# B152A.net
KiCad netlist of a schematic drawn in EAGLE
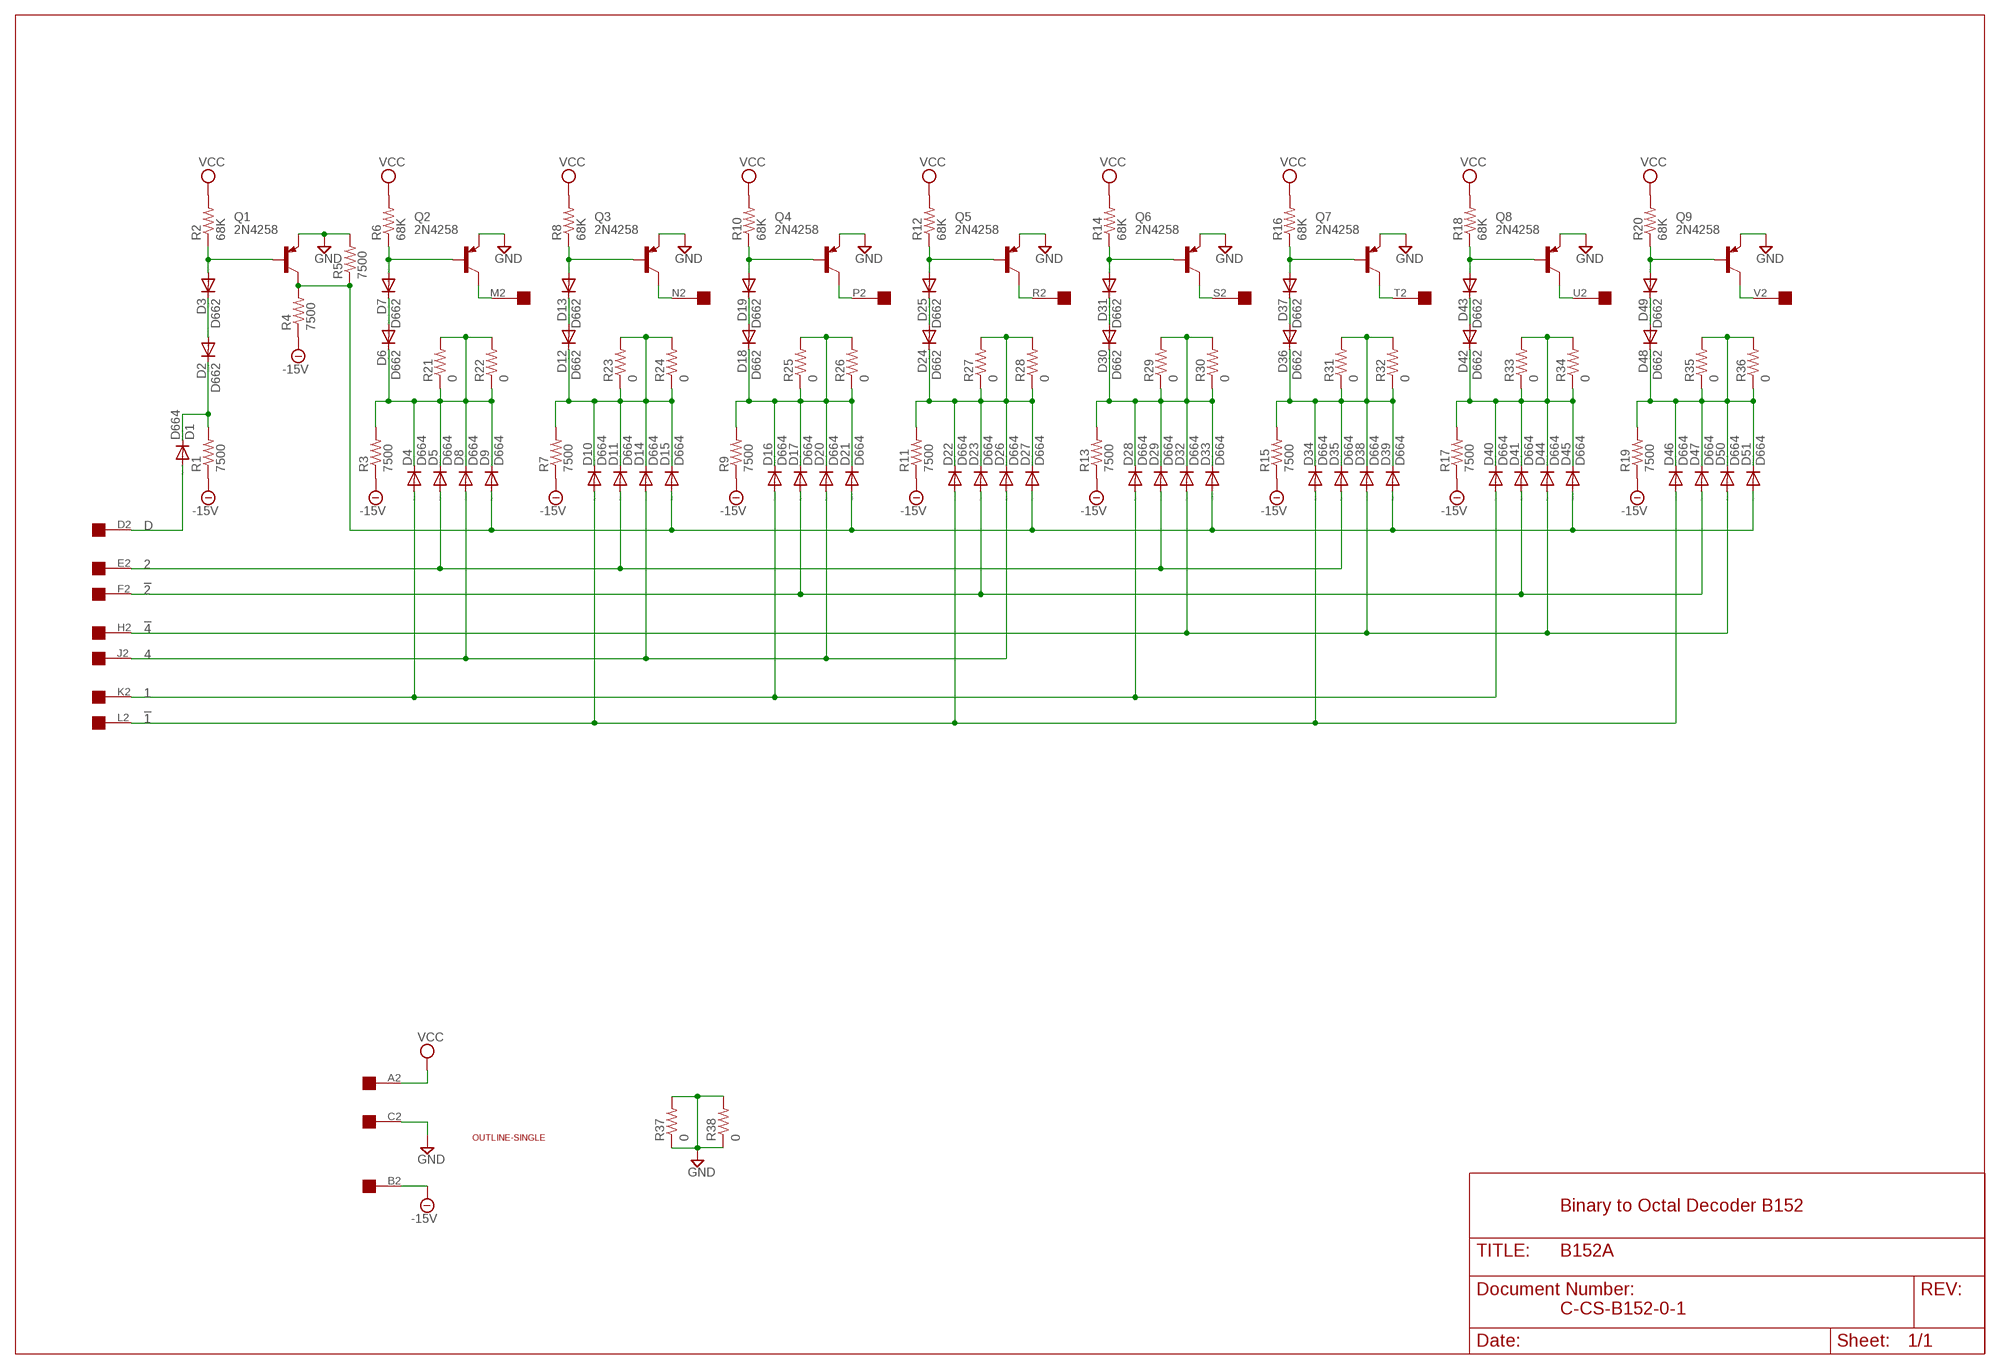
[diagram p0: schematic, sheet 1]

(export (version "E")
  (design (tool "Eeschema 10.0.6"))
  (components
    (comp (ref "D1")
      (value "D664")
      (footprint "eagle-import:DO35-10")
      (libsource (lib "eagle-import") (part "DIODE-DO35-10"))
    )
    (comp (ref "D2")
      (value "D662")
      (footprint "eagle-import:DO35-10")
      (libsource (lib "eagle-import") (part "DIODE-DO35-10"))
    )
    (comp (ref "D3")
      (value "D662")
      (footprint "eagle-import:DO35-10")
      (libsource (lib "eagle-import") (part "DIODE-DO35-10"))
    )
    (comp (ref "D4")
      (value "D664")
      (footprint "eagle-import:DO35-10")
      (libsource (lib "eagle-import") (part "DIODE-DO35-10"))
    )
    (comp (ref "D5")
      (value "D664")
      (footprint "eagle-import:DO35-10")
      (libsource (lib "eagle-import") (part "DIODE-DO35-10"))
    )
    (comp (ref "D6")
      (value "D662")
      (footprint "eagle-import:DO35-10")
      (libsource (lib "eagle-import") (part "DIODE-DO35-10"))
    )
    (comp (ref "D7")
      (value "D662")
      (footprint "eagle-import:DO35-10")
      (libsource (lib "eagle-import") (part "DIODE-DO35-10"))
    )
    (comp (ref "D8")
      (value "D664")
      (footprint "eagle-import:DO35-10")
      (libsource (lib "eagle-import") (part "DIODE-DO35-10"))
    )
    (comp (ref "D9")
      (value "D664")
      (footprint "eagle-import:DO35-10")
      (libsource (lib "eagle-import") (part "DIODE-DO35-10"))
    )
    (comp (ref "D10")
      (value "D664")
      (footprint "eagle-import:DO35-10")
      (libsource (lib "eagle-import") (part "DIODE-DO35-10"))
    )
    (comp (ref "D11")
      (value "D664")
      (footprint "eagle-import:DO35-10")
      (libsource (lib "eagle-import") (part "DIODE-DO35-10"))
    )
    (comp (ref "D12")
      (value "D662")
      (footprint "eagle-import:DO35-10")
      (libsource (lib "eagle-import") (part "DIODE-DO35-10"))
    )
    (comp (ref "D13")
      (value "D662")
      (footprint "eagle-import:DO35-10")
      (libsource (lib "eagle-import") (part "DIODE-DO35-10"))
    )
    (comp (ref "D14")
      (value "D664")
      (footprint "eagle-import:DO35-10")
      (libsource (lib "eagle-import") (part "DIODE-DO35-10"))
    )
    (comp (ref "D15")
      (value "D664")
      (footprint "eagle-import:DO35-10")
      (libsource (lib "eagle-import") (part "DIODE-DO35-10"))
    )
    (comp (ref "D16")
      (value "D664")
      (footprint "eagle-import:DO35-10")
      (libsource (lib "eagle-import") (part "DIODE-DO35-10"))
    )
    (comp (ref "D17")
      (value "D664")
      (footprint "eagle-import:DO35-10")
      (libsource (lib "eagle-import") (part "DIODE-DO35-10"))
    )
    (comp (ref "D18")
      (value "D662")
      (footprint "eagle-import:DO35-10")
      (libsource (lib "eagle-import") (part "DIODE-DO35-10"))
    )
    (comp (ref "D19")
      (value "D662")
      (footprint "eagle-import:DO35-10")
      (libsource (lib "eagle-import") (part "DIODE-DO35-10"))
    )
    (comp (ref "D20")
      (value "D664")
      (footprint "eagle-import:DO35-10")
      (libsource (lib "eagle-import") (part "DIODE-DO35-10"))
    )
    (comp (ref "D21")
      (value "D664")
      (footprint "eagle-import:DO35-10")
      (libsource (lib "eagle-import") (part "DIODE-DO35-10"))
    )
    (comp (ref "D22")
      (value "D664")
      (footprint "eagle-import:DO35-10")
      (libsource (lib "eagle-import") (part "DIODE-DO35-10"))
    )
    (comp (ref "D23")
      (value "D664")
      (footprint "eagle-import:DO35-10")
      (libsource (lib "eagle-import") (part "DIODE-DO35-10"))
    )
    (comp (ref "D24")
      (value "D662")
      (footprint "eagle-import:DO35-10")
      (libsource (lib "eagle-import") (part "DIODE-DO35-10"))
    )
    (comp (ref "D25")
      (value "D662")
      (footprint "eagle-import:DO35-10")
      (libsource (lib "eagle-import") (part "DIODE-DO35-10"))
    )
    (comp (ref "D26")
      (value "D664")
      (footprint "eagle-import:DO35-10")
      (libsource (lib "eagle-import") (part "DIODE-DO35-10"))
    )
    (comp (ref "D27")
      (value "D664")
      (footprint "eagle-import:DO35-10")
      (libsource (lib "eagle-import") (part "DIODE-DO35-10"))
    )
    (comp (ref "D28")
      (value "D664")
      (footprint "eagle-import:DO35-10")
      (libsource (lib "eagle-import") (part "DIODE-DO35-10"))
    )
    (comp (ref "D29")
      (value "D664")
      (footprint "eagle-import:DO35-10")
      (libsource (lib "eagle-import") (part "DIODE-DO35-10"))
    )
    (comp (ref "D30")
      (value "D662")
      (footprint "eagle-import:DO35-10")
      (libsource (lib "eagle-import") (part "DIODE-DO35-10"))
    )
    (comp (ref "D31")
      (value "D662")
      (footprint "eagle-import:DO35-10")
      (libsource (lib "eagle-import") (part "DIODE-DO35-10"))
    )
    (comp (ref "D32")
      (value "D664")
      (footprint "eagle-import:DO35-10")
      (libsource (lib "eagle-import") (part "DIODE-DO35-10"))
    )
    (comp (ref "D33")
      (value "D664")
      (footprint "eagle-import:DO35-10")
      (libsource (lib "eagle-import") (part "DIODE-DO35-10"))
    )
    (comp (ref "D34")
      (value "D664")
      (footprint "eagle-import:DO35-10")
      (libsource (lib "eagle-import") (part "DIODE-DO35-10"))
    )
    (comp (ref "D35")
      (value "D664")
      (footprint "eagle-import:DO35-10")
      (libsource (lib "eagle-import") (part "DIODE-DO35-10"))
    )
    (comp (ref "D36")
      (value "D662")
      (footprint "eagle-import:DO35-10")
      (libsource (lib "eagle-import") (part "DIODE-DO35-10"))
    )
    (comp (ref "D37")
      (value "D662")
      (footprint "eagle-import:DO35-10")
      (libsource (lib "eagle-import") (part "DIODE-DO35-10"))
    )
    (comp (ref "D38")
      (value "D664")
      (footprint "eagle-import:DO35-10")
      (libsource (lib "eagle-import") (part "DIODE-DO35-10"))
    )
    (comp (ref "D39")
      (value "D664")
      (footprint "eagle-import:DO35-10")
      (libsource (lib "eagle-import") (part "DIODE-DO35-10"))
    )
    (comp (ref "D40")
      (value "D664")
      (footprint "eagle-import:DO35-10")
      (libsource (lib "eagle-import") (part "DIODE-DO35-10"))
    )
    (comp (ref "D41")
      (value "D664")
      (footprint "eagle-import:DO35-10")
      (libsource (lib "eagle-import") (part "DIODE-DO35-10"))
    )
    (comp (ref "D42")
      (value "D662")
      (footprint "eagle-import:DO35-10")
      (libsource (lib "eagle-import") (part "DIODE-DO35-10"))
    )
    (comp (ref "D43")
      (value "D662")
      (footprint "eagle-import:DO35-10")
      (libsource (lib "eagle-import") (part "DIODE-DO35-10"))
    )
    (comp (ref "D44")
      (value "D664")
      (footprint "eagle-import:DO35-10")
      (libsource (lib "eagle-import") (part "DIODE-DO35-10"))
    )
    (comp (ref "D45")
      (value "D664")
      (footprint "eagle-import:DO35-10")
      (libsource (lib "eagle-import") (part "DIODE-DO35-10"))
    )
    (comp (ref "D46")
      (value "D664")
      (footprint "eagle-import:DO35-10")
      (libsource (lib "eagle-import") (part "DIODE-DO35-10"))
    )
    (comp (ref "D47")
      (value "D664")
      (footprint "eagle-import:DO35-10")
      (libsource (lib "eagle-import") (part "DIODE-DO35-10"))
    )
    (comp (ref "D48")
      (value "D662")
      (footprint "eagle-import:DO35-10")
      (libsource (lib "eagle-import") (part "DIODE-DO35-10"))
    )
    (comp (ref "D49")
      (value "D662")
      (footprint "eagle-import:DO35-10")
      (libsource (lib "eagle-import") (part "DIODE-DO35-10"))
    )
    (comp (ref "D50")
      (value "D664")
      (footprint "eagle-import:DO35-10")
      (libsource (lib "eagle-import") (part "DIODE-DO35-10"))
    )
    (comp (ref "D51")
      (value "D664")
      (footprint "eagle-import:DO35-10")
      (libsource (lib "eagle-import") (part "DIODE-DO35-10"))
    )
    (comp (ref "Q1")
      (value "2N4258")
      (footprint "eagle-import:TO5")
      (libsource (lib "eagle-import") (part "-PNP-TO5"))
    )
    (comp (ref "Q2")
      (value "2N4258")
      (footprint "eagle-import:TO5")
      (libsource (lib "eagle-import") (part "-PNP-TO5"))
    )
    (comp (ref "Q3")
      (value "2N4258")
      (footprint "eagle-import:TO5")
      (libsource (lib "eagle-import") (part "-PNP-TO5"))
    )
    (comp (ref "Q4")
      (value "2N4258")
      (footprint "eagle-import:TO5")
      (libsource (lib "eagle-import") (part "-PNP-TO5"))
    )
    (comp (ref "Q5")
      (value "2N4258")
      (footprint "eagle-import:TO5")
      (libsource (lib "eagle-import") (part "-PNP-TO5"))
    )
    (comp (ref "Q6")
      (value "2N4258")
      (footprint "eagle-import:TO5")
      (libsource (lib "eagle-import") (part "-PNP-TO5"))
    )
    (comp (ref "Q7")
      (value "2N4258")
      (footprint "eagle-import:TO5")
      (libsource (lib "eagle-import") (part "-PNP-TO5"))
    )
    (comp (ref "Q8")
      (value "2N4258")
      (footprint "eagle-import:TO5")
      (libsource (lib "eagle-import") (part "-PNP-TO5"))
    )
    (comp (ref "Q9")
      (value "2N4258")
      (footprint "eagle-import:TO5")
      (libsource (lib "eagle-import") (part "-PNP-TO5"))
    )
    (comp (ref "R1")
      (value "7500")
      (footprint "eagle-import:0207_10")
      (libsource (lib "eagle-import") (part "R-US_0207/10"))
    )
    (comp (ref "R2")
      (value "68K")
      (footprint "eagle-import:0207_10")
      (libsource (lib "eagle-import") (part "R-US_0207/10"))
    )
    (comp (ref "R3")
      (value "7500")
      (footprint "eagle-import:0207_10")
      (libsource (lib "eagle-import") (part "R-US_0207/10"))
    )
    (comp (ref "R4")
      (value "7500")
      (footprint "eagle-import:0207_10")
      (libsource (lib "eagle-import") (part "R-US_0207/10"))
    )
    (comp (ref "R5")
      (value "7500")
      (footprint "eagle-import:0207_10")
      (libsource (lib "eagle-import") (part "R-US_0207/10"))
    )
    (comp (ref "R6")
      (value "68K")
      (footprint "eagle-import:0207_10")
      (libsource (lib "eagle-import") (part "R-US_0207/10"))
    )
    (comp (ref "R7")
      (value "7500")
      (footprint "eagle-import:0207_10")
      (libsource (lib "eagle-import") (part "R-US_0207/10"))
    )
    (comp (ref "R8")
      (value "68K")
      (footprint "eagle-import:0207_10")
      (libsource (lib "eagle-import") (part "R-US_0207/10"))
    )
    (comp (ref "R9")
      (value "7500")
      (footprint "eagle-import:0207_10")
      (libsource (lib "eagle-import") (part "R-US_0207/10"))
    )
    (comp (ref "R10")
      (value "68K")
      (footprint "eagle-import:0207_10")
      (libsource (lib "eagle-import") (part "R-US_0207/10"))
    )
    (comp (ref "R11")
      (value "7500")
      (footprint "eagle-import:0207_10")
      (libsource (lib "eagle-import") (part "R-US_0207/10"))
    )
    (comp (ref "R12")
      (value "68K")
      (footprint "eagle-import:0207_10")
      (libsource (lib "eagle-import") (part "R-US_0207/10"))
    )
    (comp (ref "R13")
      (value "7500")
      (footprint "eagle-import:0207_10")
      (libsource (lib "eagle-import") (part "R-US_0207/10"))
    )
    (comp (ref "R14")
      (value "68K")
      (footprint "eagle-import:0207_10")
      (libsource (lib "eagle-import") (part "R-US_0207/10"))
    )
    (comp (ref "R15")
      (value "7500")
      (footprint "eagle-import:0207_10")
      (libsource (lib "eagle-import") (part "R-US_0207/10"))
    )
    (comp (ref "R16")
      (value "68K")
      (footprint "eagle-import:0207_10")
      (libsource (lib "eagle-import") (part "R-US_0207/10"))
    )
    (comp (ref "R17")
      (value "7500")
      (footprint "eagle-import:0207_10")
      (libsource (lib "eagle-import") (part "R-US_0207/10"))
    )
    (comp (ref "R18")
      (value "68K")
      (footprint "eagle-import:0207_10")
      (libsource (lib "eagle-import") (part "R-US_0207/10"))
    )
    (comp (ref "R19")
      (value "7500")
      (footprint "eagle-import:0207_10")
      (libsource (lib "eagle-import") (part "R-US_0207/10"))
    )
    (comp (ref "R20")
      (value "68K")
      (footprint "eagle-import:0207_10")
      (libsource (lib "eagle-import") (part "R-US_0207/10"))
    )
    (comp (ref "R21")
      (value "0")
      (footprint "eagle-import:0207_10")
      (libsource (lib "eagle-import") (part "R-US_0207/10"))
    )
    (comp (ref "R22")
      (value "0")
      (footprint "eagle-import:0207_10")
      (libsource (lib "eagle-import") (part "R-US_0207/10"))
    )
    (comp (ref "R23")
      (value "0")
      (footprint "eagle-import:0207_10")
      (libsource (lib "eagle-import") (part "R-US_0207/10"))
    )
    (comp (ref "R24")
      (value "0")
      (footprint "eagle-import:0207_10")
      (libsource (lib "eagle-import") (part "R-US_0207/10"))
    )
    (comp (ref "R25")
      (value "0")
      (footprint "eagle-import:0207_10")
      (libsource (lib "eagle-import") (part "R-US_0207/10"))
    )
    (comp (ref "R26")
      (value "0")
      (footprint "eagle-import:0207_10")
      (libsource (lib "eagle-import") (part "R-US_0207/10"))
    )
    (comp (ref "R27")
      (value "0")
      (footprint "eagle-import:0207_10")
      (libsource (lib "eagle-import") (part "R-US_0207/10"))
    )
    (comp (ref "R28")
      (value "0")
      (footprint "eagle-import:0207_10")
      (libsource (lib "eagle-import") (part "R-US_0207/10"))
    )
    (comp (ref "R29")
      (value "0")
      (footprint "eagle-import:0207_10")
      (libsource (lib "eagle-import") (part "R-US_0207/10"))
    )
    (comp (ref "R30")
      (value "0")
      (footprint "eagle-import:0207_10")
      (libsource (lib "eagle-import") (part "R-US_0207/10"))
    )
    (comp (ref "R31")
      (value "0")
      (footprint "eagle-import:0207_10")
      (libsource (lib "eagle-import") (part "R-US_0207/10"))
    )
    (comp (ref "R32")
      (value "0")
      (footprint "eagle-import:0207_10")
      (libsource (lib "eagle-import") (part "R-US_0207/10"))
    )
    (comp (ref "R33")
      (value "0")
      (footprint "eagle-import:0207_10")
      (libsource (lib "eagle-import") (part "R-US_0207/10"))
    )
    (comp (ref "R34")
      (value "0")
      (footprint "eagle-import:0207_10")
      (libsource (lib "eagle-import") (part "R-US_0207/10"))
    )
    (comp (ref "R35")
      (value "0")
      (footprint "eagle-import:0207_10")
      (libsource (lib "eagle-import") (part "R-US_0207/10"))
    )
    (comp (ref "R36")
      (value "0")
      (footprint "eagle-import:0207_10")
      (libsource (lib "eagle-import") (part "R-US_0207/10"))
    )
    (comp (ref "R37")
      (value "0")
      (footprint "eagle-import:0207_10")
      (libsource (lib "eagle-import") (part "R-US_0207/10"))
    )
    (comp (ref "R38")
      (value "0")
      (footprint "eagle-import:0207_10")
      (libsource (lib "eagle-import") (part "R-US_0207/10"))
    )
    (comp (ref "U$1")
      (value "OUTLINE-SINGLE")
      (footprint "eagle-import:SINGLE")
      (libsource (lib "eagle-import") (part "OUTLINE-SINGLE"))
    )
    (comp (ref "U$2")
      (value "EDGE-1")
      (footprint "eagle-import:EDGE-CON1")
      (libsource (lib "eagle-import") (part "EDGE-1"))
    )
  )
  (nets
    (net (code "1") (name "-15V") (class "Default")
      (node (ref "R1") (pin "1") (pinfunction "1_1") (pintype "passive"))
      (node (ref "R11") (pin "1") (pinfunction "1_1") (pintype "passive"))
      (node (ref "R13") (pin "1") (pinfunction "1_1") (pintype "passive"))
      (node (ref "R15") (pin "1") (pinfunction "1_1") (pintype "passive"))
      (node (ref "R17") (pin "1") (pinfunction "1_1") (pintype "passive"))
      (node (ref "R19") (pin "1") (pinfunction "1_1") (pintype "passive"))
      (node (ref "R3") (pin "1") (pinfunction "1_1") (pintype "passive"))
      (node (ref "R4") (pin "1") (pinfunction "1_1") (pintype "passive"))
      (node (ref "R7") (pin "1") (pinfunction "1_1") (pintype "passive"))
      (node (ref "R9") (pin "1") (pinfunction "1_1") (pintype "passive"))
      (node (ref "U$2") (pin "B2") (pinfunction "1_B2") (pintype "bidirectional"))
    )
    (net (code "2") (name "/1") (class "Default")
      (node (ref "D16") (pin "A") (pinfunction "A_A") (pintype "passive"))
      (node (ref "D28") (pin "A") (pinfunction "A_A") (pintype "passive"))
      (node (ref "D4") (pin "A") (pinfunction "A_A") (pintype "passive"))
      (node (ref "D40") (pin "A") (pinfunction "A_A") (pintype "passive"))
      (node (ref "U$2") (pin "K2") (pinfunction "1_K2") (pintype "bidirectional"))
    )
    (net (code "3") (name "/2") (class "Default")
      (node (ref "D11") (pin "A") (pinfunction "A_A") (pintype "passive"))
      (node (ref "D29") (pin "A") (pinfunction "A_A") (pintype "passive"))
      (node (ref "D35") (pin "A") (pinfunction "A_A") (pintype "passive"))
      (node (ref "D5") (pin "A") (pinfunction "A_A") (pintype "passive"))
      (node (ref "U$2") (pin "E2") (pinfunction "1_E2") (pintype "bidirectional"))
    )
    (net (code "4") (name "/4") (class "Default")
      (node (ref "D14") (pin "A") (pinfunction "A_A") (pintype "passive"))
      (node (ref "D20") (pin "A") (pinfunction "A_A") (pintype "passive"))
      (node (ref "D26") (pin "A") (pinfunction "A_A") (pintype "passive"))
      (node (ref "D8") (pin "A") (pinfunction "A_A") (pintype "passive"))
      (node (ref "U$2") (pin "J2") (pinfunction "1_J2") (pintype "bidirectional"))
    )
    (net (code "5") (name "/D") (class "Default")
      (node (ref "D1") (pin "A") (pinfunction "A_A") (pintype "passive"))
      (node (ref "U$2") (pin "D2") (pinfunction "1_D2") (pintype "bidirectional"))
    )
    (net (code "6") (name "/~{1}") (class "Default")
      (node (ref "D10") (pin "A") (pinfunction "A_A") (pintype "passive"))
      (node (ref "D22") (pin "A") (pinfunction "A_A") (pintype "passive"))
      (node (ref "D34") (pin "A") (pinfunction "A_A") (pintype "passive"))
      (node (ref "D46") (pin "A") (pinfunction "A_A") (pintype "passive"))
      (node (ref "U$2") (pin "L2") (pinfunction "1_L2") (pintype "bidirectional"))
    )
    (net (code "7") (name "/~{2}") (class "Default")
      (node (ref "D17") (pin "A") (pinfunction "A_A") (pintype "passive"))
      (node (ref "D23") (pin "A") (pinfunction "A_A") (pintype "passive"))
      (node (ref "D41") (pin "A") (pinfunction "A_A") (pintype "passive"))
      (node (ref "D47") (pin "A") (pinfunction "A_A") (pintype "passive"))
      (node (ref "U$2") (pin "F2") (pinfunction "1_F2") (pintype "bidirectional"))
    )
    (net (code "8") (name "/~{4}") (class "Default")
      (node (ref "D32") (pin "A") (pinfunction "A_A") (pintype "passive"))
      (node (ref "D38") (pin "A") (pinfunction "A_A") (pintype "passive"))
      (node (ref "D44") (pin "A") (pinfunction "A_A") (pintype "passive"))
      (node (ref "D50") (pin "A") (pinfunction "A_A") (pintype "passive"))
      (node (ref "U$2") (pin "H2") (pinfunction "1_H2") (pintype "bidirectional"))
    )
    (net (code "9") (name "GND") (class "Default")
      (node (ref "Q1") (pin "1") (pinfunction "E_1") (pintype "passive"))
      (node (ref "Q2") (pin "1") (pinfunction "E_1") (pintype "passive"))
      (node (ref "Q3") (pin "1") (pinfunction "E_1") (pintype "passive"))
      (node (ref "Q4") (pin "1") (pinfunction "E_1") (pintype "passive"))
      (node (ref "Q5") (pin "1") (pinfunction "E_1") (pintype "passive"))
      (node (ref "Q6") (pin "1") (pinfunction "E_1") (pintype "passive"))
      (node (ref "Q7") (pin "1") (pinfunction "E_1") (pintype "passive"))
      (node (ref "Q8") (pin "1") (pinfunction "E_1") (pintype "passive"))
      (node (ref "Q9") (pin "1") (pinfunction "E_1") (pintype "passive"))
      (node (ref "R37") (pin "1") (pinfunction "1_1") (pintype "passive"))
      (node (ref "R37") (pin "2") (pinfunction "2_2") (pintype "passive"))
      (node (ref "R38") (pin "1") (pinfunction "1_1") (pintype "passive"))
      (node (ref "R38") (pin "2") (pinfunction "2_2") (pintype "passive"))
      (node (ref "R5") (pin "2") (pinfunction "2_2") (pintype "passive"))
      (node (ref "U$2") (pin "C2") (pinfunction "1_C2") (pintype "bidirectional"))
    )
    (net (code "10") (name "Net-(D1-PadC)") (class "Default")
      (node (ref "D1") (pin "C") (pinfunction "C_C") (pintype "passive"))
      (node (ref "D2") (pin "C") (pinfunction "C_C") (pintype "passive"))
      (node (ref "R1") (pin "2") (pinfunction "2_2") (pintype "passive"))
    )
    (net (code "11") (name "Net-(D2-PadA)") (class "Default")
      (node (ref "D2") (pin "A") (pinfunction "A_A") (pintype "passive"))
      (node (ref "D3") (pin "C") (pinfunction "C_C") (pintype "passive"))
    )
    (net (code "12") (name "Net-(D4-PadC)") (class "Default")
      (node (ref "D4") (pin "C") (pinfunction "C_C") (pintype "passive"))
      (node (ref "D5") (pin "C") (pinfunction "C_C") (pintype "passive"))
      (node (ref "D6") (pin "C") (pinfunction "C_C") (pintype "passive"))
      (node (ref "D8") (pin "C") (pinfunction "C_C") (pintype "passive"))
      (node (ref "D9") (pin "C") (pinfunction "C_C") (pintype "passive"))
      (node (ref "R21") (pin "1") (pinfunction "1_1") (pintype "passive"))
      (node (ref "R21") (pin "2") (pinfunction "2_2") (pintype "passive"))
      (node (ref "R22") (pin "1") (pinfunction "1_1") (pintype "passive"))
      (node (ref "R22") (pin "2") (pinfunction "2_2") (pintype "passive"))
      (node (ref "R3") (pin "2") (pinfunction "2_2") (pintype "passive"))
    )
    (net (code "13") (name "Net-(D6-PadA)") (class "Default")
      (node (ref "D6") (pin "A") (pinfunction "A_A") (pintype "passive"))
      (node (ref "D7") (pin "C") (pinfunction "C_C") (pintype "passive"))
    )
    (net (code "14") (name "Net-(D10-PadC)") (class "Default")
      (node (ref "D10") (pin "C") (pinfunction "C_C") (pintype "passive"))
      (node (ref "D11") (pin "C") (pinfunction "C_C") (pintype "passive"))
      (node (ref "D12") (pin "C") (pinfunction "C_C") (pintype "passive"))
      (node (ref "D14") (pin "C") (pinfunction "C_C") (pintype "passive"))
      (node (ref "D15") (pin "C") (pinfunction "C_C") (pintype "passive"))
      (node (ref "R23") (pin "1") (pinfunction "1_1") (pintype "passive"))
      (node (ref "R23") (pin "2") (pinfunction "2_2") (pintype "passive"))
      (node (ref "R24") (pin "1") (pinfunction "1_1") (pintype "passive"))
      (node (ref "R24") (pin "2") (pinfunction "2_2") (pintype "passive"))
      (node (ref "R7") (pin "2") (pinfunction "2_2") (pintype "passive"))
    )
    (net (code "15") (name "Net-(D12-PadA)") (class "Default")
      (node (ref "D12") (pin "A") (pinfunction "A_A") (pintype "passive"))
      (node (ref "D13") (pin "C") (pinfunction "C_C") (pintype "passive"))
    )
    (net (code "16") (name "Net-(D16-PadC)") (class "Default")
      (node (ref "D16") (pin "C") (pinfunction "C_C") (pintype "passive"))
      (node (ref "D17") (pin "C") (pinfunction "C_C") (pintype "passive"))
      (node (ref "D18") (pin "C") (pinfunction "C_C") (pintype "passive"))
      (node (ref "D20") (pin "C") (pinfunction "C_C") (pintype "passive"))
      (node (ref "D21") (pin "C") (pinfunction "C_C") (pintype "passive"))
      (node (ref "R25") (pin "1") (pinfunction "1_1") (pintype "passive"))
      (node (ref "R25") (pin "2") (pinfunction "2_2") (pintype "passive"))
      (node (ref "R26") (pin "1") (pinfunction "1_1") (pintype "passive"))
      (node (ref "R26") (pin "2") (pinfunction "2_2") (pintype "passive"))
      (node (ref "R9") (pin "2") (pinfunction "2_2") (pintype "passive"))
    )
    (net (code "17") (name "Net-(D18-PadA)") (class "Default")
      (node (ref "D18") (pin "A") (pinfunction "A_A") (pintype "passive"))
      (node (ref "D19") (pin "C") (pinfunction "C_C") (pintype "passive"))
    )
    (net (code "18") (name "Net-(D22-PadC)") (class "Default")
      (node (ref "D22") (pin "C") (pinfunction "C_C") (pintype "passive"))
      (node (ref "D23") (pin "C") (pinfunction "C_C") (pintype "passive"))
      (node (ref "D24") (pin "C") (pinfunction "C_C") (pintype "passive"))
      (node (ref "D26") (pin "C") (pinfunction "C_C") (pintype "passive"))
      (node (ref "D27") (pin "C") (pinfunction "C_C") (pintype "passive"))
      (node (ref "R11") (pin "2") (pinfunction "2_2") (pintype "passive"))
      (node (ref "R27") (pin "1") (pinfunction "1_1") (pintype "passive"))
      (node (ref "R27") (pin "2") (pinfunction "2_2") (pintype "passive"))
      (node (ref "R28") (pin "1") (pinfunction "1_1") (pintype "passive"))
      (node (ref "R28") (pin "2") (pinfunction "2_2") (pintype "passive"))
    )
    (net (code "19") (name "Net-(D24-PadA)") (class "Default")
      (node (ref "D24") (pin "A") (pinfunction "A_A") (pintype "passive"))
      (node (ref "D25") (pin "C") (pinfunction "C_C") (pintype "passive"))
    )
    (net (code "20") (name "Net-(D28-PadC)") (class "Default")
      (node (ref "D28") (pin "C") (pinfunction "C_C") (pintype "passive"))
      (node (ref "D29") (pin "C") (pinfunction "C_C") (pintype "passive"))
      (node (ref "D30") (pin "C") (pinfunction "C_C") (pintype "passive"))
      (node (ref "D32") (pin "C") (pinfunction "C_C") (pintype "passive"))
      (node (ref "D33") (pin "C") (pinfunction "C_C") (pintype "passive"))
      (node (ref "R13") (pin "2") (pinfunction "2_2") (pintype "passive"))
      (node (ref "R29") (pin "1") (pinfunction "1_1") (pintype "passive"))
      (node (ref "R29") (pin "2") (pinfunction "2_2") (pintype "passive"))
      (node (ref "R30") (pin "1") (pinfunction "1_1") (pintype "passive"))
      (node (ref "R30") (pin "2") (pinfunction "2_2") (pintype "passive"))
    )
    (net (code "21") (name "Net-(D30-PadA)") (class "Default")
      (node (ref "D30") (pin "A") (pinfunction "A_A") (pintype "passive"))
      (node (ref "D31") (pin "C") (pinfunction "C_C") (pintype "passive"))
    )
    (net (code "22") (name "Net-(D34-PadC)") (class "Default")
      (node (ref "D34") (pin "C") (pinfunction "C_C") (pintype "passive"))
      (node (ref "D35") (pin "C") (pinfunction "C_C") (pintype "passive"))
      (node (ref "D36") (pin "C") (pinfunction "C_C") (pintype "passive"))
      (node (ref "D38") (pin "C") (pinfunction "C_C") (pintype "passive"))
      (node (ref "D39") (pin "C") (pinfunction "C_C") (pintype "passive"))
      (node (ref "R15") (pin "2") (pinfunction "2_2") (pintype "passive"))
      (node (ref "R31") (pin "1") (pinfunction "1_1") (pintype "passive"))
      (node (ref "R31") (pin "2") (pinfunction "2_2") (pintype "passive"))
      (node (ref "R32") (pin "1") (pinfunction "1_1") (pintype "passive"))
      (node (ref "R32") (pin "2") (pinfunction "2_2") (pintype "passive"))
    )
    (net (code "23") (name "Net-(D36-PadA)") (class "Default")
      (node (ref "D36") (pin "A") (pinfunction "A_A") (pintype "passive"))
      (node (ref "D37") (pin "C") (pinfunction "C_C") (pintype "passive"))
    )
    (net (code "24") (name "Net-(D40-PadC)") (class "Default")
      (node (ref "D40") (pin "C") (pinfunction "C_C") (pintype "passive"))
      (node (ref "D41") (pin "C") (pinfunction "C_C") (pintype "passive"))
      (node (ref "D42") (pin "C") (pinfunction "C_C") (pintype "passive"))
      (node (ref "D44") (pin "C") (pinfunction "C_C") (pintype "passive"))
      (node (ref "D45") (pin "C") (pinfunction "C_C") (pintype "passive"))
      (node (ref "R17") (pin "2") (pinfunction "2_2") (pintype "passive"))
      (node (ref "R33") (pin "1") (pinfunction "1_1") (pintype "passive"))
      (node (ref "R33") (pin "2") (pinfunction "2_2") (pintype "passive"))
      (node (ref "R34") (pin "1") (pinfunction "1_1") (pintype "passive"))
      (node (ref "R34") (pin "2") (pinfunction "2_2") (pintype "passive"))
    )
    (net (code "25") (name "Net-(D42-PadA)") (class "Default")
      (node (ref "D42") (pin "A") (pinfunction "A_A") (pintype "passive"))
      (node (ref "D43") (pin "C") (pinfunction "C_C") (pintype "passive"))
    )
    (net (code "26") (name "Net-(D46-PadC)") (class "Default")
      (node (ref "D46") (pin "C") (pinfunction "C_C") (pintype "passive"))
      (node (ref "D47") (pin "C") (pinfunction "C_C") (pintype "passive"))
      (node (ref "D48") (pin "C") (pinfunction "C_C") (pintype "passive"))
      (node (ref "D50") (pin "C") (pinfunction "C_C") (pintype "passive"))
      (node (ref "D51") (pin "C") (pinfunction "C_C") (pintype "passive"))
      (node (ref "R19") (pin "2") (pinfunction "2_2") (pintype "passive"))
      (node (ref "R35") (pin "1") (pinfunction "1_1") (pintype "passive"))
      (node (ref "R35") (pin "2") (pinfunction "2_2") (pintype "passive"))
      (node (ref "R36") (pin "1") (pinfunction "1_1") (pintype "passive"))
      (node (ref "R36") (pin "2") (pinfunction "2_2") (pintype "passive"))
    )
    (net (code "27") (name "Net-(D48-PadA)") (class "Default")
      (node (ref "D48") (pin "A") (pinfunction "A_A") (pintype "passive"))
      (node (ref "D49") (pin "C") (pinfunction "C_C") (pintype "passive"))
    )
    (net (code "28") (name "Net-(Q1-B)") (class "Default")
      (node (ref "D3") (pin "A") (pinfunction "A_A") (pintype "passive"))
      (node (ref "Q1") (pin "2") (pinfunction "B_2") (pintype "passive"))
      (node (ref "R2") (pin "1") (pinfunction "1_1") (pintype "passive"))
    )
    (net (code "29") (name "Net-(Q1-C)") (class "Default")
      (node (ref "D15") (pin "A") (pinfunction "A_A") (pintype "passive"))
      (node (ref "D21") (pin "A") (pinfunction "A_A") (pintype "passive"))
      (node (ref "D27") (pin "A") (pinfunction "A_A") (pintype "passive"))
      (node (ref "D33") (pin "A") (pinfunction "A_A") (pintype "passive"))
      (node (ref "D39") (pin "A") (pinfunction "A_A") (pintype "passive"))
      (node (ref "D45") (pin "A") (pinfunction "A_A") (pintype "passive"))
      (node (ref "D51") (pin "A") (pinfunction "A_A") (pintype "passive"))
      (node (ref "D9") (pin "A") (pinfunction "A_A") (pintype "passive"))
      (node (ref "Q1") (pin "3") (pinfunction "C_3") (pintype "passive"))
      (node (ref "R4") (pin "2") (pinfunction "2_2") (pintype "passive"))
      (node (ref "R5") (pin "1") (pinfunction "1_1") (pintype "passive"))
    )
    (net (code "30") (name "Net-(Q2-B)") (class "Default")
      (node (ref "D7") (pin "A") (pinfunction "A_A") (pintype "passive"))
      (node (ref "Q2") (pin "2") (pinfunction "B_2") (pintype "passive"))
      (node (ref "R6") (pin "1") (pinfunction "1_1") (pintype "passive"))
    )
    (net (code "31") (name "Net-(Q2-C)") (class "Default")
      (node (ref "Q2") (pin "3") (pinfunction "C_3") (pintype "passive"))
      (node (ref "U$2") (pin "M2") (pinfunction "1_M2") (pintype "bidirectional"))
    )
    (net (code "32") (name "Net-(Q3-B)") (class "Default")
      (node (ref "D13") (pin "A") (pinfunction "A_A") (pintype "passive"))
      (node (ref "Q3") (pin "2") (pinfunction "B_2") (pintype "passive"))
      (node (ref "R8") (pin "1") (pinfunction "1_1") (pintype "passive"))
    )
    (net (code "33") (name "Net-(Q3-C)") (class "Default")
      (node (ref "Q3") (pin "3") (pinfunction "C_3") (pintype "passive"))
      (node (ref "U$2") (pin "N2") (pinfunction "1_N2") (pintype "bidirectional"))
    )
    (net (code "34") (name "Net-(Q4-B)") (class "Default")
      (node (ref "D19") (pin "A") (pinfunction "A_A") (pintype "passive"))
      (node (ref "Q4") (pin "2") (pinfunction "B_2") (pintype "passive"))
      (node (ref "R10") (pin "1") (pinfunction "1_1") (pintype "passive"))
    )
    (net (code "35") (name "Net-(Q4-C)") (class "Default")
      (node (ref "Q4") (pin "3") (pinfunction "C_3") (pintype "passive"))
      (node (ref "U$2") (pin "P2") (pinfunction "1_P2") (pintype "bidirectional"))
    )
    (net (code "36") (name "Net-(Q5-B)") (class "Default")
      (node (ref "D25") (pin "A") (pinfunction "A_A") (pintype "passive"))
      (node (ref "Q5") (pin "2") (pinfunction "B_2") (pintype "passive"))
      (node (ref "R12") (pin "1") (pinfunction "1_1") (pintype "passive"))
    )
    (net (code "37") (name "Net-(Q5-C)") (class "Default")
      (node (ref "Q5") (pin "3") (pinfunction "C_3") (pintype "passive"))
      (node (ref "U$2") (pin "R2") (pinfunction "1_R2") (pintype "bidirectional"))
    )
    (net (code "38") (name "Net-(Q6-B)") (class "Default")
      (node (ref "D31") (pin "A") (pinfunction "A_A") (pintype "passive"))
      (node (ref "Q6") (pin "2") (pinfunction "B_2") (pintype "passive"))
      (node (ref "R14") (pin "1") (pinfunction "1_1") (pintype "passive"))
    )
    (net (code "39") (name "Net-(Q6-C)") (class "Default")
      (node (ref "Q6") (pin "3") (pinfunction "C_3") (pintype "passive"))
      (node (ref "U$2") (pin "S2") (pinfunction "1_S2") (pintype "bidirectional"))
    )
    (net (code "40") (name "Net-(Q7-B)") (class "Default")
      (node (ref "D37") (pin "A") (pinfunction "A_A") (pintype "passive"))
      (node (ref "Q7") (pin "2") (pinfunction "B_2") (pintype "passive"))
      (node (ref "R16") (pin "1") (pinfunction "1_1") (pintype "passive"))
    )
    (net (code "41") (name "Net-(Q7-C)") (class "Default")
      (node (ref "Q7") (pin "3") (pinfunction "C_3") (pintype "passive"))
      (node (ref "U$2") (pin "T2") (pinfunction "1_T2") (pintype "bidirectional"))
    )
    (net (code "42") (name "Net-(Q8-B)") (class "Default")
      (node (ref "D43") (pin "A") (pinfunction "A_A") (pintype "passive"))
      (node (ref "Q8") (pin "2") (pinfunction "B_2") (pintype "passive"))
      (node (ref "R18") (pin "1") (pinfunction "1_1") (pintype "passive"))
    )
    (net (code "43") (name "Net-(Q8-C)") (class "Default")
      (node (ref "Q8") (pin "3") (pinfunction "C_3") (pintype "passive"))
      (node (ref "U$2") (pin "U2") (pinfunction "1_U2") (pintype "bidirectional"))
    )
    (net (code "44") (name "Net-(Q9-B)") (class "Default")
      (node (ref "D49") (pin "A") (pinfunction "A_A") (pintype "passive"))
      (node (ref "Q9") (pin "2") (pinfunction "B_2") (pintype "passive"))
      (node (ref "R20") (pin "1") (pinfunction "1_1") (pintype "passive"))
    )
    (net (code "45") (name "Net-(Q9-C)") (class "Default")
      (node (ref "Q9") (pin "3") (pinfunction "C_3") (pintype "passive"))
      (node (ref "U$2") (pin "V2") (pinfunction "1_V2") (pintype "bidirectional"))
    )
    (net (code "46") (name "VCC") (class "Default")
      (node (ref "R10") (pin "2") (pinfunction "2_2") (pintype "passive"))
      (node (ref "R12") (pin "2") (pinfunction "2_2") (pintype "passive"))
      (node (ref "R14") (pin "2") (pinfunction "2_2") (pintype "passive"))
      (node (ref "R16") (pin "2") (pinfunction "2_2") (pintype "passive"))
      (node (ref "R18") (pin "2") (pinfunction "2_2") (pintype "passive"))
      (node (ref "R2") (pin "2") (pinfunction "2_2") (pintype "passive"))
      (node (ref "R20") (pin "2") (pinfunction "2_2") (pintype "passive"))
      (node (ref "R6") (pin "2") (pinfunction "2_2") (pintype "passive"))
      (node (ref "R8") (pin "2") (pinfunction "2_2") (pintype "passive"))
      (node (ref "U$2") (pin "A2") (pinfunction "1_A2") (pintype "bidirectional"))
    )
  )
)
